# POWER_CONTROLLER3.net
KiCad netlist of a schematic drawn in Altium Designer
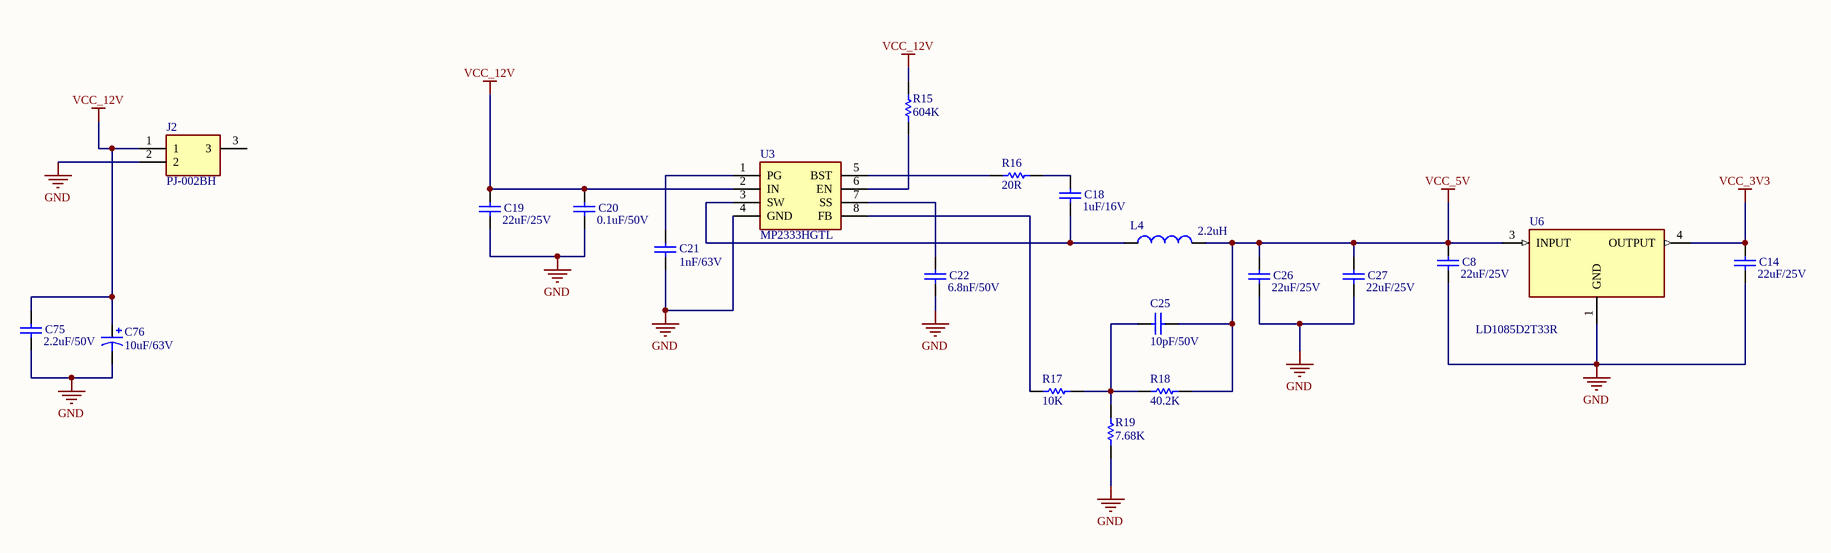
[diagram p0: POWER_CONTROLLER3.SchDoc]

(export (version "E")
  (design (tool "Eeschema 10.0.6"))
  (components
    (comp (ref "C8")
      (value "22uF/25V")
      (footprint "1210C")
      (description "Multilayer Ceramic Capacitors MLCC - SMD/SMT 1210 25VDC 22uF 20% X7R AEC-Q200")
      (fields (field (name "MFR") "Taiyo Yuden") (field (name "MFR PART NO") "TMK325B7226MMHP"))
      (libsource (lib "Miscellaneous Devices") (part "Cap"))
    )
    (comp (ref "C14")
      (value "22uF/25V")
      (footprint "1210C")
      (description "Multilayer Ceramic Capacitors MLCC - SMD/SMT 1210 25VDC 22uF 20% X7R AEC-Q200")
      (fields (field (name "MFR") "Taiyo Yuden") (field (name "MFR PART NO") "TMK325B7226MMHP"))
      (libsource (lib "Miscellaneous Devices") (part "Cap"))
    )
    (comp (ref "C18")
      (value "1uF/16V")
      (footprint "0603C")
      (description "Multilayer Ceramic Capacitors MLCC - SMD/SMT 16volts 1uF X7R 10%")
      (fields (field (name "MFR") "KEMET") (field (name "MFR PART NO") "C0603C105K4RAC7411"))
      (libsource (lib "Miscellaneous Devices") (part "Cap"))
    )
    (comp (ref "C19")
      (value "22uF/25V")
      (footprint "1210C")
      (description "Multilayer Ceramic Capacitors MLCC - SMD/SMT 1210 25VDC 22uF 20% X7R AEC-Q200")
      (fields (field (name "MFR") "Taiyo Yuden") (field (name "MFR PART NO") "TMK325B7226MMHP"))
      (libsource (lib "Miscellaneous Devices") (part "Cap"))
    )
    (comp (ref "C20")
      (value "0.1uF/50V")
      (footprint "0603C")
      (description "Multilayer Ceramic Capacitors MLCC - SMD/SMT 50V 0.1uF 0603 X7R 20%")
      (fields (field (name "MFR") "KEMET") (field (name "MFR PART NO") "C0603C104M5RACTU"))
      (libsource (lib "Miscellaneous Devices") (part "Cap"))
    )
    (comp (ref "C21")
      (value "1nF/63V")
      (footprint "0603C")
      (description "Multilayer Ceramic Capacitors MLCC - SMD/SMT 63V 1000pF 0603 X7R 10% AEC-Q200")
      (fields (field (name "MFR") "KEMET") (field (name "MFR PART NO") "80-C0603C102KMREAUTO"))
      (libsource (lib "Miscellaneous Devices") (part "Cap"))
    )
    (comp (ref "C22")
      (value "6.8nF/50V")
      (footprint "0603C")
      (description "Multilayer Ceramic Capacitors MLCC - SMD/SMT 0603 50VDC 6.8nF 5% C0G AEC-Q200")
      (fields (field (name "MFR") "TDK") (field (name "MFR PART NO") "CGA3E2C0G1H682J080AE"))
      (libsource (lib "Miscellaneous Devices") (part "Cap"))
    )
    (comp (ref "C25")
      (value "10pF/50V")
      (footprint "0603C")
      (description "Multilayer Ceramic Capacitors MLCC - SMD/SMT 50V 10pF 0603 C0G 5% AEC-Q200")
      (fields (field (name "MFR") "KEMET") (field (name "MFR PART NO") "C0603C100J5GACAUTO"))
      (libsource (lib "Miscellaneous Devices") (part "Cap"))
    )
    (comp (ref "C26")
      (value "22uF/25V")
      (footprint "1210C")
      (description "Multilayer Ceramic Capacitors MLCC - SMD/SMT 1210 25VDC 22uF 20% X7R AEC-Q200")
      (fields (field (name "MFR") "Taiyo Yuden") (field (name "MFR PART NO") "TMK325B7226MMHP"))
      (libsource (lib "Miscellaneous Devices") (part "Cap"))
    )
    (comp (ref "C27")
      (value "22uF/25V")
      (footprint "1210C")
      (description "Multilayer Ceramic Capacitors MLCC - SMD/SMT 1210 25VDC 22uF 20% X7R AEC-Q200")
      (fields (field (name "MFR") "Taiyo Yuden") (field (name "MFR PART NO") "TMK325B7226MMHP"))
      (libsource (lib "Miscellaneous Devices") (part "Cap"))
    )
    (comp (ref "C75")
      (value "2.2uF/50V")
      (footprint "0603C")
      (description "Multilayer Ceramic Capacitors MLCC - SMD/SMT 0603 2.2uF 20% 50VDC X5R")
      (fields (field (name "MFR") "Murata Electronics") (field (name "MFR PART NO") "GRM188R61H225ME11J"))
      (libsource (lib "Miscellaneous Devices") (part "Cap"))
    )
    (comp (ref "C76")
      (value "10uF/63V")
      (footprint "EEE-FN1J100L")
      (description "Polarized Capacitor (Radial)")
      (fields (field (name "MFR") "Panasonic") (field (name "MFR PART NO") "EEE-FN1J100L"))
      (libsource (lib "Miscellaneous Devices") (part "Cap Pol1"))
    )
    (comp (ref "J2")
      (value "PJ-002BH")
      (footprint "PJ002BH")
      (description "Connector")
      (fields (field (name "MOUSER PART NUMBER") "490-PJ-002BH"))
      (libsource (lib "SamacSys") (part "PJ-002BH"))
    )
    (comp (ref "L4")
      (value "2.2uH")
      (footprint "IHLP1616BZER2R2M5A")
      (description "Fixed Inductors 2.2uH 20% High Temp AEC-Q200")
      (fields (field (name "MFR") "Vishay / Dale") (field (name "MFR PART NO") "IHLP1616BZER2R2M5A"))
      (libsource (lib "de20") (part "INDUCTOR"))
    )
    (comp (ref "R15")
      (value "604K")
      (footprint "0603R")
      (description "Thick Film Resistors - SMD 0603 1% 604Kohm Anti-Sulfur AEC-Q200")
      (fields (field (name "MFR") "Panasonic") (field (name "MFR PART NO") "ERJ-U03F6043V"))
      (libsource (lib "Miscellaneous Devices") (part "Res1"))
    )
    (comp (ref "R16")
      (value "20R")
      (footprint "0603R")
      (description "Thick Film Resistors - SMD 0603 0.25W 1% 20ohm AEC-Q200")
      (fields (field (name "MFR") "Panasonic") (field (name "MFR PART NO") "ERJ-UP3F20R0V"))
      (libsource (lib "Miscellaneous Devices") (part "Res1"))
    )
    (comp (ref "R17")
      (value "10K")
      (footprint "0603R")
      (description "Thick Film Resistors - SMD 0603 10Kohms 1% Anti-Sulfur AEC-Q200")
      (fields (field (name "MFR") "ROHM Semiconductor") (field (name "MFR PART NO") "SFR03EZPF1002"))
      (libsource (lib "Miscellaneous Devices") (part "Res1"))
    )
    (comp (ref "R18")
      (value "40.2K")
      (footprint "0603R")
      (description "Thick Film Resistors - SMD 0603 Anti-Surge Res. 0.1%, 40.2Koh")
      (fields (field (name "MFR") "Panasonic") (field (name "MFR PART NO") "ERJ-PB3B4022V"))
      (libsource (lib "Miscellaneous Devices") (part "Res1"))
    )
    (comp (ref "R19")
      (value "7.68K")
      (footprint "0603R")
      (description "Thick Film Resistors - SMD 0603 Anti-Surge Res. 0.1%, 7.68Koh")
      (fields (field (name "MFR") "Panasonic") (field (name "MFR PART NO") "ERJ-PB3B7681V"))
      (libsource (lib "Miscellaneous Devices") (part "Res1"))
    )
    (comp (ref "U3")
      (value "MP2333HGTL")
      (footprint "MP2333HGTL-P")
      (description "Switching Voltage Regulators High-Efficiency, 3A, 18V, 1200kHz, Synchronous, Step-Down Converter")
      (fields
        (field (name "MFR") "Monolithic Power Systems (MPS)")
        (field (name "MFR PART NO") "MP2333HGTL-P")
      )
      (libsource (lib "*") (part "MP2333HGTL"))
    )
    (comp (ref "U6")
      (value "LD1085D2T33R")
      (footprint "LD1085D2T33R")
      (description "Integrated Circuit")
      (fields
        (field (name "MFR") "STMicroelectronics")
        (field (name "STOCKIEST PART NO") "511-LD1085D2T33-TR")
      )
      (libsource (lib "*") (part "LD1085D2T33R"))
    )
  )
  (nets
    (net (code "1") (name "GND") (class "Default")
      (node (ref "C14") (pin "1") (pinfunction "1_1") (pintype "passive"))
      (node (ref "C19") (pin "1") (pinfunction "1_1") (pintype "passive"))
      (node (ref "C20") (pin "1") (pinfunction "1_1") (pintype "passive"))
      (node (ref "C21") (pin "1") (pinfunction "1_1") (pintype "passive"))
      (node (ref "C22") (pin "1") (pinfunction "1_1") (pintype "passive"))
      (node (ref "C26") (pin "1") (pinfunction "1_1") (pintype "passive"))
      (node (ref "C27") (pin "1") (pinfunction "1_1") (pintype "passive"))
      (node (ref "C75") (pin "1") (pinfunction "1_1") (pintype "passive"))
      (node (ref "C76") (pin "2") (pinfunction "2_2") (pintype "passive"))
      (node (ref "C8") (pin "1") (pinfunction "1_1") (pintype "passive"))
      (node (ref "J2") (pin "2") (pinfunction "2_2") (pintype "passive"))
      (node (ref "R19") (pin "2") (pinfunction "2_2") (pintype "passive"))
      (node (ref "U3") (pin "4") (pinfunction "GND_4") (pintype "passive"))
      (node (ref "U6") (pin "1") (pinfunction "GND_1") (pintype "power_in"))
    )
    (net (code "2") (name "Net-(C18-Pad2)") (class "Default")
      (node (ref "C18") (pin "2") (pinfunction "2_2") (pintype "passive"))
      (node (ref "R16") (pin "2") (pinfunction "2_2") (pintype "passive"))
    )
    (net (code "3") (name "Net-(C25-Pad2)") (class "Default")
      (node (ref "C25") (pin "2") (pinfunction "2_2") (pintype "passive"))
      (node (ref "R17") (pin "1") (pinfunction "1_1") (pintype "passive"))
      (node (ref "R18") (pin "1") (pinfunction "1_1") (pintype "passive"))
      (node (ref "R19") (pin "1") (pinfunction "1_1") (pintype "passive"))
    )
    (net (code "4") (name "Net-(U3-BST)") (class "Default")
      (node (ref "R16") (pin "1") (pinfunction "1_1") (pintype "passive"))
      (node (ref "U3") (pin "5") (pinfunction "BST_5") (pintype "passive"))
    )
    (net (code "5") (name "Net-(U3-EN)") (class "Default")
      (node (ref "R15") (pin "1") (pinfunction "1_1") (pintype "passive"))
      (node (ref "U3") (pin "6") (pinfunction "EN_6") (pintype "passive"))
    )
    (net (code "6") (name "Net-(U3-FB)") (class "Default")
      (node (ref "R17") (pin "2") (pinfunction "2_2") (pintype "passive"))
      (node (ref "U3") (pin "8") (pinfunction "FB_8") (pintype "passive"))
    )
    (net (code "7") (name "Net-(U3-PG)") (class "Default")
      (node (ref "C21") (pin "2") (pinfunction "2_2") (pintype "passive"))
      (node (ref "U3") (pin "1") (pinfunction "PG_1") (pintype "passive"))
    )
    (net (code "8") (name "Net-(U3-SS)") (class "Default")
      (node (ref "C22") (pin "2") (pinfunction "2_2") (pintype "passive"))
      (node (ref "U3") (pin "7") (pinfunction "SS_7") (pintype "passive"))
    )
    (net (code "9") (name "Net-(U3-SW)") (class "Default")
      (node (ref "C18") (pin "1") (pinfunction "1_1") (pintype "passive"))
      (node (ref "L4") (pin "1") (pinfunction "1_1") (pintype "passive"))
      (node (ref "U3") (pin "3") (pinfunction "SW_3") (pintype "passive"))
    )
    (net (code "10") (name "VCC_3V3") (class "Default")
      (node (ref "C14") (pin "2") (pinfunction "2_2") (pintype "passive"))
      (node (ref "U6") (pin "4") (pinfunction "OUTPUT_4") (pintype "output"))
    )
    (net (code "11") (name "VCC_5V") (class "Default")
      (node (ref "C25") (pin "1") (pinfunction "1_1") (pintype "passive"))
      (node (ref "C26") (pin "2") (pinfunction "2_2") (pintype "passive"))
      (node (ref "C27") (pin "2") (pinfunction "2_2") (pintype "passive"))
      (node (ref "C8") (pin "2") (pinfunction "2_2") (pintype "passive"))
      (node (ref "L4") (pin "2") (pinfunction "2_2") (pintype "passive"))
      (node (ref "R18") (pin "2") (pinfunction "2_2") (pintype "passive"))
      (node (ref "U6") (pin "3") (pinfunction "INPUT_3") (pintype "input"))
    )
    (net (code "12") (name "VCC_12V") (class "Default")
      (node (ref "C19") (pin "2") (pinfunction "2_2") (pintype "passive"))
      (node (ref "C20") (pin "2") (pinfunction "2_2") (pintype "passive"))
      (node (ref "C75") (pin "2") (pinfunction "2_2") (pintype "passive"))
      (node (ref "C76") (pin "1") (pinfunction "1_1") (pintype "passive"))
      (node (ref "J2") (pin "1") (pinfunction "1_1") (pintype "passive"))
      (node (ref "R15") (pin "2") (pinfunction "2_2") (pintype "passive"))
      (node (ref "U3") (pin "2") (pinfunction "IN_2") (pintype "passive"))
    )
    (net (code "13") (name "unconnected-(J2-Pad3)") (class "Default")
      (node (ref "J2") (pin "3") (pinfunction "3_3") (pintype "passive"))
    )
  )
)
